# CH585M-R1.net
KiCad netlist of a schematic drawn in Altium Designer
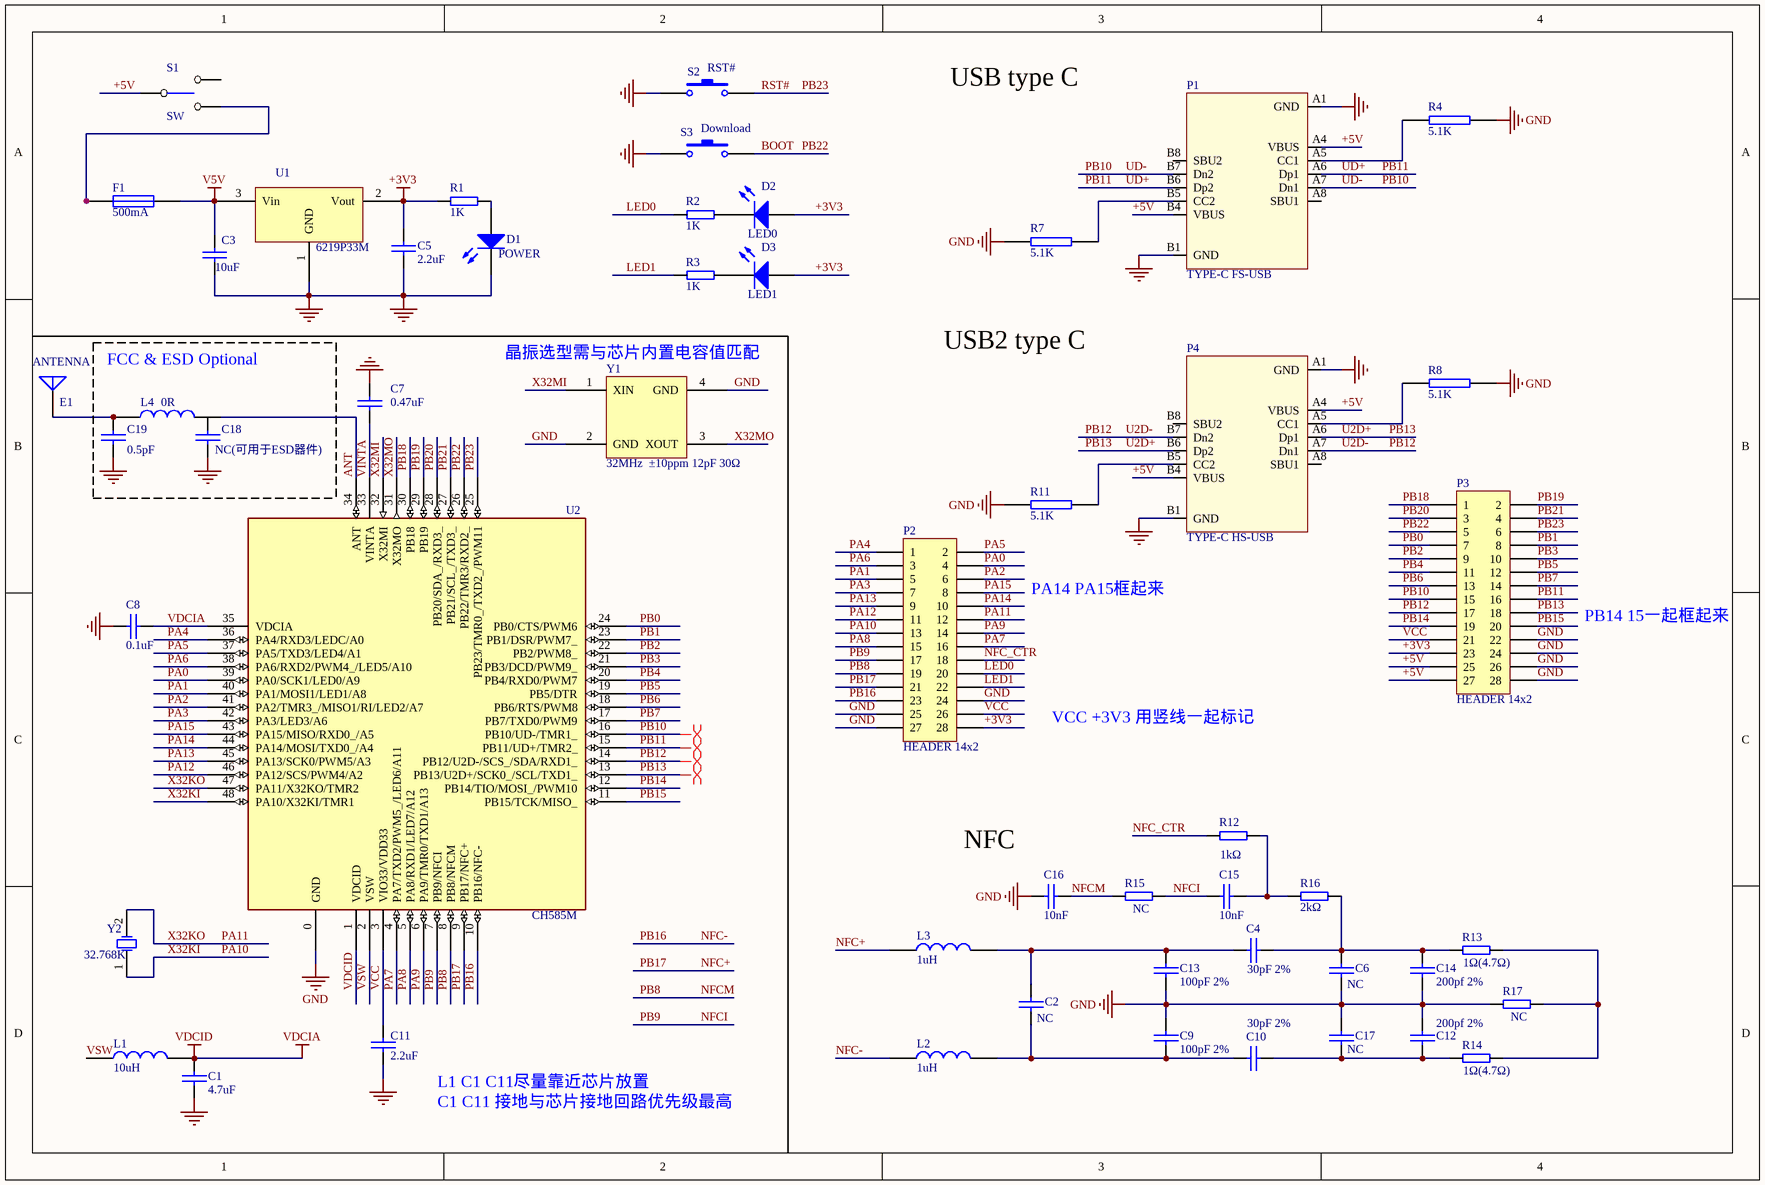
[diagram p0: CH585M-R1.SchDoc]

(export (version "E")
  (design (tool "Eeschema 10.0.6"))
  (components
    (comp (ref "C1")
      (value "4.7uF")
      (footprint "0402_C")
      (description "Capacitor")
      (libsource (lib "") (part "CAP_1"))
    )
    (comp (ref "C2")
      (value "NC")
      (footprint "0402_C")
      (description "Capacitor")
      (libsource (lib "wch_sch_others") (part "CAP"))
    )
    (comp (ref "C3")
      (value "10uF")
      (footprint "0603_C")
      (description "Capacitor")
      (libsource (lib "*") (part "CAP"))
    )
    (comp (ref "C4")
      (value "30pF 2%")
      (footprint "0402_C")
      (description "Capacitor")
      (libsource (lib "wch_sch_others") (part "CAP"))
    )
    (comp (ref "C5")
      (value "2.2uF")
      (footprint "0402_C")
      (description "Capacitor")
      (libsource (lib "*") (part "CAP"))
    )
    (comp (ref "C6")
      (value "NC")
      (footprint "0402_C")
      (description "Capacitor")
      (libsource (lib "wch_sch_others") (part "CAP"))
    )
    (comp (ref "C7")
      (value "0.47uF")
      (footprint "0402_C")
      (description "Capacitor")
      (libsource (lib "*") (part "CAP"))
    )
    (comp (ref "C8")
      (value "0.1uF")
      (footprint "0402_C")
      (description "Capacitor")
      (libsource (lib "*") (part "CAP"))
    )
    (comp (ref "C9")
      (value "100pF 2%")
      (footprint "0402_C")
      (description "Capacitor")
      (libsource (lib "wch_sch_others") (part "CAP"))
    )
    (comp (ref "C10")
      (value "30pF 2%")
      (footprint "0402_C")
      (description "Capacitor")
      (libsource (lib "wch_sch_others") (part "CAP"))
    )
    (comp (ref "C11")
      (value "2.2uF")
      (footprint "0402_C")
      (description "Capacitor")
      (libsource (lib "*") (part "CAP"))
    )
    (comp (ref "C12")
      (value "200pf 2%")
      (footprint "0402_C")
      (description "Capacitor")
      (libsource (lib "wch_sch_others") (part "CAP"))
    )
    (comp (ref "C13")
      (value "100pF 2%")
      (footprint "0402_C")
      (description "Capacitor")
      (libsource (lib "wch_sch_others") (part "CAP"))
    )
    (comp (ref "C14")
      (value "200pf 2%")
      (footprint "0402_C")
      (description "Capacitor")
      (libsource (lib "wch_sch_others") (part "CAP"))
    )
    (comp (ref "C15")
      (value "10nF")
      (footprint "0402_C")
      (description "Capacitor")
      (libsource (lib "wch_sch_others") (part "CAP"))
    )
    (comp (ref "C16")
      (value "10nF")
      (footprint "0402_C")
      (description "Capacitor")
      (libsource (lib "wch_sch_others") (part "CAP"))
    )
    (comp (ref "C17")
      (value "NC")
      (footprint "0402_C")
      (description "Capacitor")
      (libsource (lib "wch_sch_others") (part "CAP"))
    )
    (comp (ref "C18")
      (value "NC(可用于ESD器件)")
      (footprint "0402_C")
      (description "Capacitor")
      (libsource (lib "*") (part "CAP"))
    )
    (comp (ref "C19")
      (value "0.5pF")
      (footprint "0402_C")
      (description "Capacitor")
      (libsource (lib "") (part "CAP_1"))
    )
    (comp (ref "D1")
      (value "POWER")
      (footprint "0603+")
      (description "Typical INFRARED GaAs LED")
      (fields (field (name "PUBLISHER") "Altium Limited"))
      (libsource (lib "") (part "LED0_1"))
    )
    (comp (ref "D2")
      (value "LED0")
      (footprint "0603+")
      (description "Typical INFRARED GaAs LED")
      (fields (field (name "PUBLISHER") "Altium Limited"))
      (libsource (lib "Miscellaneous Devices") (part "LED0"))
    )
    (comp (ref "D3")
      (value "LED1")
      (footprint "0603+")
      (description "Typical INFRARED GaAs LED")
      (fields (field (name "PUBLISHER") "Altium Limited"))
      (libsource (lib "Miscellaneous Devices") (part "LED0"))
    )
    (comp (ref "E1")
      (value "ANTENNA")
      (footprint "ANT-F-1-2.4G-1.6mmFR4")
      (description "Generic Antenna")
      (libsource (lib "*") (part "ANTENNA"))
    )
    (comp (ref "F1")
      (value "500mA")
      (footprint "0603")
      (description "Fuse")
      (libsource (lib "*") (part "FUSE1"))
    )
    (comp (ref "L1") (value "10uH") (footprint "SMD_2x2mm") (libsource (lib "*") (part "INDUCTOR")))
    (comp (ref "L2") (value "1uH") (footprint "0603") (libsource (lib "*") (part "INDUCTOR")))
    (comp (ref "L3") (value "1uH") (footprint "0603") (libsource (lib "*") (part "INDUCTOR")))
    (comp (ref "L4") (value "0R") (footprint "SMD_2x2mm") (libsource (lib "*") (part "INDUCTOR")))
    (comp (ref "P1")
      (value "TYPE-C FS-USB")
      (footprint "TYPE-C-Receptacle-2.0")
      (description "Type-C USB2.0 母座")
      (libsource (lib "Miscellaneous SCH Lib") (part "TYPE-C-Receptacle-2.0"))
    )
    (comp (ref "P2")
      (value "HEADER 14x2")
      (footprint "MYPCB:IDC28-2.54MM")
      (description "Header, 14-Pin, Dual row")
      (libsource (lib "wch_sch_others") (part "HEADER 14x2"))
    )
    (comp (ref "P3")
      (value "HEADER 14x2")
      (footprint "MYPCB:IDC28-2.54MM")
      (description "Header, 14-Pin, Dual row")
      (libsource (lib "wch_sch_others") (part "HEADER 14x2"))
    )
    (comp (ref "P4")
      (value "TYPE-C HS-USB")
      (footprint "TYPE-C-Receptacle-2.0")
      (description "Type-C USB2.0 母座")
      (libsource (lib "Miscellaneous SCH Lib") (part "TYPE-C-Receptacle-2.0"))
    )
    (comp (ref "R1") (value "1K") (footprint "0402") (libsource (lib "wch_sch_others") (part "RES")))
    (comp (ref "R2") (value "1K") (footprint "0402") (libsource (lib "wch_sch_others") (part "RES")))
    (comp (ref "R3") (value "1K") (footprint "0402") (libsource (lib "wch_sch_others") (part "RES")))
    (comp (ref "R4") (value "5.1K") (footprint "0402") (libsource (lib "*") (part "RES2")))
    (comp (ref "R7") (value "5.1K") (footprint "0402") (libsource (lib "*") (part "RES2")))
    (comp (ref "R8") (value "5.1K") (footprint "0402") (libsource (lib "*") (part "RES2")))
    (comp (ref "R11") (value "5.1K") (footprint "0402") (libsource (lib "*") (part "RES2")))
    (comp (ref "R12") (value "1kΩ") (footprint "0402") (libsource (lib "") (part "RES_1")))
    (comp (ref "R13") (value "1Ω(4.7Ω)") (footprint "0402") (libsource (lib "") (part "RES_1")))
    (comp (ref "R14") (value "1Ω(4.7Ω)") (footprint "0402") (libsource (lib "") (part "RES_1")))
    (comp (ref "R15") (value "NC") (footprint "0402") (libsource (lib "") (part "RES_1")))
    (comp (ref "R16") (value "2kΩ") (footprint "0402") (libsource (lib "") (part "RES_1")))
    (comp (ref "R17") (value "NC") (footprint "0402") (libsource (lib "") (part "RES_1")))
    (comp (ref "S1") (value "SW") (footprint "SW1") (libsource (lib "MYSCH") (part "SW")))
    (comp (ref "S2")
      (value "RST#")
      (footprint "SMD_6.1x3.65x2.5mm-KEY")
      (description "Switch")
      (fields (field (name "PUBLISHER") "Altium Limited"))
      (libsource (lib "*") (part "SW-PB"))
    )
    (comp (ref "S3")
      (value "Download")
      (footprint "SMD_6.1x3.65x2.5mm-KEY")
      (description "Switch")
      (fields (field (name "PUBLISHER") "Altium Limited"))
      (libsource (lib "*") (part "SW-PB"))
    )
    (comp (ref "U1")
      (value "6219P33M")
      (footprint "SOT-23")
      (libsource (lib "wch_sch_others") (part "6219P33M"))
    )
    (comp (ref "U2")
      (value "CH585M")
      (footprint "QFN48_5X5")
      (description "RISC-V MCU with BLE/HSUSB/USB/NFC/ADC/PWM/2*SPI/I2C/4*UART/LCD")
      (libsource (lib "CHXXX") (part "CH585M"))
    )
    (comp (ref "Y1")
      (value "32MHz  ±10ppm 12pF 30Ω")
      (footprint "XT3225")
      (libsource (lib "wch_sch_others") (part "晶体"))
    )
    (comp (ref "Y2")
      (value "32.768K")
      (footprint "fc-135")
      (description "Crystal Oscillator")
      (fields (field (name "PUBLISHER") "Altium Limited"))
      (libsource (lib "*") (part "XTAL"))
    )
  )
  (nets
    (net (code "1") (name "+3V3") (class "Default")
      (node (ref "C5") (pin "1") (pinfunction "1_1") (pintype "passive"))
      (node (ref "D2") (pin "1") (pinfunction "A_1") (pintype "passive"))
      (node (ref "D3") (pin "1") (pinfunction "A_1") (pintype "passive"))
      (node (ref "P2") (pin "28") (pinfunction "28_28") (pintype "passive"))
      (node (ref "P3") (pin "23") (pinfunction "23_23") (pintype "passive"))
      (node (ref "R1") (pin "2") (pintype "passive"))
      (node (ref "U1") (pin "2") (pinfunction "Vout_2") (pintype "passive"))
    )
    (net (code "2") (name "/+5V") (class "Default")
      (node (ref "P1") (pin "A4") (pinfunction "VBUS_A4") (pintype "passive"))
      (node (ref "P1") (pin "B4") (pinfunction "VBUS_B4") (pintype "passive"))
      (node (ref "P3") (pin "25") (pinfunction "25_25") (pintype "passive"))
      (node (ref "P3") (pin "27") (pinfunction "27_27") (pintype "passive"))
      (node (ref "P4") (pin "A4") (pinfunction "VBUS_A4") (pintype "passive"))
      (node (ref "P4") (pin "B4") (pinfunction "VBUS_B4") (pintype "passive"))
      (node (ref "S1") (pin "1") (pinfunction "1_1") (pintype "passive"))
    )
    (net (code "3") (name "/ANT") (class "Default")
      (node (ref "L4") (pin "2") (pinfunction "2_2") (pintype "passive"))
      (node (ref "U2") (pin "34") (pinfunction "ANT_34") (pintype "bidirectional"))
    )
    (net (code "4") (name "/BOOT") (class "Default")
      (node (ref "P3") (pin "5") (pinfunction "5_5") (pintype "passive"))
      (node (ref "S3") (pin "2") (pinfunction "2_2") (pintype "passive"))
      (node (ref "U2") (pin "26") (pinfunction "PB22/TMR3/RXD2__26") (pintype "bidirectional"))
    )
    (net (code "5") (name "/LED0") (class "Default")
      (node (ref "P2") (pin "20") (pinfunction "20_20") (pintype "passive"))
      (node (ref "R2") (pin "1") (pintype "passive"))
    )
    (net (code "6") (name "/LED1") (class "Default")
      (node (ref "P2") (pin "22") (pinfunction "22_22") (pintype "passive"))
      (node (ref "R3") (pin "1") (pintype "passive"))
    )
    (net (code "7") (name "/NFC+") (class "Default")
      (node (ref "L3") (pin "1") (pinfunction "1_1") (pintype "passive"))
      (node (ref "P2") (pin "21") (pinfunction "21_21") (pintype "passive"))
      (node (ref "U2") (pin "9") (pinfunction "PB17/NFC+_9") (pintype "bidirectional"))
    )
    (net (code "8") (name "/NFC-") (class "Default")
      (node (ref "L2") (pin "1") (pinfunction "1_1") (pintype "passive"))
      (node (ref "P2") (pin "23") (pinfunction "23_23") (pintype "passive"))
      (node (ref "U2") (pin "10") (pinfunction "PB16/NFC-_10") (pintype "bidirectional"))
    )
    (net (code "9") (name "/NFCI") (class "Default")
      (node (ref "C15") (pin "1") (pinfunction "1_1") (pintype "passive"))
      (node (ref "P2") (pin "17") (pinfunction "17_17") (pintype "passive"))
      (node (ref "R15") (pin "1") (pintype "passive"))
      (node (ref "U2") (pin "7") (pinfunction "PB9/NFCI_7") (pintype "bidirectional"))
    )
    (net (code "10") (name "/NFCM") (class "Default")
      (node (ref "C16") (pin "1") (pinfunction "1_1") (pintype "passive"))
      (node (ref "P2") (pin "19") (pinfunction "19_19") (pintype "passive"))
      (node (ref "R15") (pin "2") (pintype "passive"))
      (node (ref "U2") (pin "8") (pinfunction "PB8/NFCM_8") (pintype "bidirectional"))
    )
    (net (code "11") (name "/NFC_CTR") (class "Default")
      (node (ref "P2") (pin "18") (pinfunction "18_18") (pintype "passive"))
      (node (ref "R12") (pin "2") (pintype "passive"))
    )
    (net (code "12") (name "/PA0") (class "Default")
      (node (ref "P2") (pin "4") (pinfunction "4_4") (pintype "passive"))
      (node (ref "U2") (pin "39") (pinfunction "PA0/SCK1/LED0/A9_39") (pintype "bidirectional"))
    )
    (net (code "13") (name "/PA1") (class "Default")
      (node (ref "P2") (pin "5") (pinfunction "5_5") (pintype "passive"))
      (node (ref "U2") (pin "40") (pinfunction "PA1/MOSI1/LED1/A8_40") (pintype "bidirectional"))
    )
    (net (code "14") (name "/PA2") (class "Default")
      (node (ref "P2") (pin "6") (pinfunction "6_6") (pintype "passive"))
      (node (ref "U2") (pin "41") (pinfunction "PA2/TMR3_/MISO1/RI/LED2/A7_41") (pintype "bidirectional"))
    )
    (net (code "15") (name "/PA3") (class "Default")
      (node (ref "P2") (pin "7") (pinfunction "7_7") (pintype "passive"))
      (node (ref "U2") (pin "42") (pinfunction "PA3/LED3/A6_42") (pintype "bidirectional"))
    )
    (net (code "16") (name "/PA4") (class "Default")
      (node (ref "P2") (pin "1") (pinfunction "1_1") (pintype "passive"))
      (node (ref "U2") (pin "36") (pinfunction "PA4/RXD3/LEDC/A0_36") (pintype "bidirectional"))
    )
    (net (code "17") (name "/PA5") (class "Default")
      (node (ref "P2") (pin "2") (pinfunction "2_2") (pintype "passive"))
      (node (ref "U2") (pin "37") (pinfunction "PA5/TXD3/LED4/A1_37") (pintype "bidirectional"))
    )
    (net (code "18") (name "/PA6") (class "Default")
      (node (ref "P2") (pin "3") (pinfunction "3_3") (pintype "passive"))
      (node (ref "U2") (pin "38") (pinfunction "PA6/RXD2/PWM4_/LED5/A10_38") (pintype "bidirectional"))
    )
    (net (code "19") (name "/PA7") (class "Default")
      (node (ref "P2") (pin "16") (pinfunction "16_16") (pintype "passive"))
      (node (ref "U2") (pin "4") (pinfunction "PA7/TXD2/PWM5_/LED6/A11_4") (pintype "bidirectional"))
    )
    (net (code "20") (name "/PA8") (class "Default")
      (node (ref "P2") (pin "15") (pinfunction "15_15") (pintype "passive"))
      (node (ref "U2") (pin "5") (pinfunction "PA8/RXD1/LED7/A12_5") (pintype "bidirectional"))
    )
    (net (code "21") (name "/PA9") (class "Default")
      (node (ref "P2") (pin "14") (pinfunction "14_14") (pintype "passive"))
      (node (ref "U2") (pin "6") (pinfunction "PA9/TMR0/TXD1/A13_6") (pintype "bidirectional"))
    )
    (net (code "22") (name "/PA10") (class "Default")
      (node (ref "P2") (pin "13") (pinfunction "13_13") (pintype "passive"))
      (node (ref "U2") (pin "48") (pinfunction "PA10/X32KI/TMR1_48") (pintype "bidirectional"))
      (node (ref "Y2") (pin "1") (pinfunction "OSC1_1") (pintype "passive"))
    )
    (net (code "23") (name "/PA11") (class "Default")
      (node (ref "P2") (pin "12") (pinfunction "12_12") (pintype "passive"))
      (node (ref "U2") (pin "47") (pinfunction "PA11/X32KO/TMR2_47") (pintype "bidirectional"))
      (node (ref "Y2") (pin "2") (pinfunction "OSC2_2") (pintype "passive"))
    )
    (net (code "24") (name "/PA12") (class "Default")
      (node (ref "P2") (pin "11") (pinfunction "11_11") (pintype "passive"))
      (node (ref "U2") (pin "46") (pinfunction "PA12/SCS/PWM4/A2_46") (pintype "bidirectional"))
    )
    (net (code "25") (name "/PA13") (class "Default")
      (node (ref "P2") (pin "9") (pinfunction "9_9") (pintype "passive"))
      (node (ref "U2") (pin "45") (pinfunction "PA13/SCK0/PWM5/A3_45") (pintype "bidirectional"))
    )
    (net (code "26") (name "/PA14") (class "Default")
      (node (ref "P2") (pin "10") (pinfunction "10_10") (pintype "passive"))
      (node (ref "U2") (pin "44") (pinfunction "PA14/MOSI/TXD0_/A4_44") (pintype "bidirectional"))
    )
    (net (code "27") (name "/PA15") (class "Default")
      (node (ref "P2") (pin "8") (pinfunction "8_8") (pintype "passive"))
      (node (ref "U2") (pin "43") (pinfunction "PA15/MISO/RXD0_/A5_43") (pintype "bidirectional"))
    )
    (net (code "28") (name "/PB0") (class "Default")
      (node (ref "P3") (pin "7") (pinfunction "7_7") (pintype "passive"))
      (node (ref "U2") (pin "24") (pinfunction "PB0/CTS/PWM6_24") (pintype "bidirectional"))
    )
    (net (code "29") (name "/PB1") (class "Default")
      (node (ref "P3") (pin "8") (pinfunction "8_8") (pintype "passive"))
      (node (ref "U2") (pin "23") (pinfunction "PB1/DSR/PWM7__23") (pintype "bidirectional"))
    )
    (net (code "30") (name "/PB2") (class "Default")
      (node (ref "P3") (pin "9") (pinfunction "9_9") (pintype "passive"))
      (node (ref "U2") (pin "22") (pinfunction "PB2/PWM8__22") (pintype "bidirectional"))
    )
    (net (code "31") (name "/PB3") (class "Default")
      (node (ref "P3") (pin "10") (pinfunction "10_10") (pintype "passive"))
      (node (ref "U2") (pin "21") (pinfunction "PB3/DCD/PWM9__21") (pintype "bidirectional"))
    )
    (net (code "32") (name "/PB4") (class "Default")
      (node (ref "P3") (pin "11") (pinfunction "11_11") (pintype "passive"))
      (node (ref "U2") (pin "20") (pinfunction "PB4/RXD0/PWM7_20") (pintype "bidirectional"))
    )
    (net (code "33") (name "/PB5") (class "Default")
      (node (ref "P3") (pin "12") (pinfunction "12_12") (pintype "passive"))
      (node (ref "U2") (pin "19") (pinfunction "PB5/DTR_19") (pintype "bidirectional"))
    )
    (net (code "34") (name "/PB6") (class "Default")
      (node (ref "P3") (pin "13") (pinfunction "13_13") (pintype "passive"))
      (node (ref "U2") (pin "18") (pinfunction "PB6/RTS/PWM8_18") (pintype "bidirectional"))
    )
    (net (code "35") (name "/PB7") (class "Default")
      (node (ref "P3") (pin "14") (pinfunction "14_14") (pintype "passive"))
      (node (ref "U2") (pin "17") (pinfunction "PB7/TXD0/PWM9_17") (pintype "bidirectional"))
    )
    (net (code "36") (name "/PB10") (class "Default")
      (node (ref "P1") (pin "A7") (pinfunction "Dn1_A7") (pintype "passive"))
      (node (ref "P1") (pin "B7") (pinfunction "Dn2_B7") (pintype "passive"))
      (node (ref "P3") (pin "15") (pinfunction "15_15") (pintype "passive"))
      (node (ref "U2") (pin "16") (pinfunction "PB10/UD-/TMR1__16") (pintype "bidirectional"))
    )
    (net (code "37") (name "/PB11") (class "Default")
      (node (ref "P1") (pin "A6") (pinfunction "Dp1_A6") (pintype "passive"))
      (node (ref "P1") (pin "B6") (pinfunction "Dp2_B6") (pintype "passive"))
      (node (ref "P3") (pin "16") (pinfunction "16_16") (pintype "passive"))
      (node (ref "U2") (pin "15") (pinfunction "PB11/UD+/TMR2__15") (pintype "bidirectional"))
    )
    (net (code "38") (name "/PB12") (class "Default")
      (node (ref "P3") (pin "17") (pinfunction "17_17") (pintype "passive"))
      (node (ref "P4") (pin "A7") (pinfunction "Dn1_A7") (pintype "passive"))
      (node (ref "P4") (pin "B7") (pinfunction "Dn2_B7") (pintype "passive"))
      (node (ref "U2") (pin "14") (pinfunction "PB12/U2D-/SCS_/SDA/RXD1__14") (pintype "bidirectional"))
    )
    (net (code "39") (name "/PB13") (class "Default")
      (node (ref "P3") (pin "18") (pinfunction "18_18") (pintype "passive"))
      (node (ref "P4") (pin "A6") (pinfunction "Dp1_A6") (pintype "passive"))
      (node (ref "P4") (pin "B6") (pinfunction "Dp2_B6") (pintype "passive"))
      (node (ref "U2") (pin "13") (pinfunction "PB13/U2D+/SCK0_/SCL/TXD1__13") (pintype "bidirectional"))
    )
    (net (code "40") (name "/PB14") (class "Default")
      (node (ref "P3") (pin "19") (pinfunction "19_19") (pintype "passive"))
      (node (ref "U2") (pin "12") (pinfunction "PB14/TIO/MOSI_/PWM10_12") (pintype "bidirectional"))
    )
    (net (code "41") (name "/PB15") (class "Default")
      (node (ref "P3") (pin "20") (pinfunction "20_20") (pintype "passive"))
      (node (ref "U2") (pin "11") (pinfunction "PB15/TCK/MISO__11") (pintype "bidirectional"))
    )
    (net (code "42") (name "/PB18") (class "Default")
      (node (ref "P3") (pin "1") (pinfunction "1_1") (pintype "passive"))
      (node (ref "U2") (pin "30") (pinfunction "PB18_30") (pintype "bidirectional"))
    )
    (net (code "43") (name "/PB19") (class "Default")
      (node (ref "P3") (pin "2") (pinfunction "2_2") (pintype "passive"))
      (node (ref "U2") (pin "29") (pinfunction "PB19_29") (pintype "bidirectional"))
    )
    (net (code "44") (name "/PB20") (class "Default")
      (node (ref "P3") (pin "3") (pinfunction "3_3") (pintype "passive"))
      (node (ref "U2") (pin "28") (pinfunction "PB20/SDA_/RXD3__28") (pintype "bidirectional"))
    )
    (net (code "45") (name "/PB21") (class "Default")
      (node (ref "P3") (pin "4") (pinfunction "4_4") (pintype "passive"))
      (node (ref "U2") (pin "27") (pinfunction "PB21/SCL_/TXD3__27") (pintype "bidirectional"))
    )
    (net (code "46") (name "/PB23") (class "Default")
      (node (ref "P3") (pin "6") (pinfunction "6_6") (pintype "passive"))
      (node (ref "S2") (pin "2") (pinfunction "2_2") (pintype "passive"))
      (node (ref "U2") (pin "25") (pinfunction "PB23/TMR0_/TXD2_/PWM11_25") (pintype "bidirectional"))
    )
    (net (code "47") (name "/VCC") (class "Default")
      (node (ref "C11") (pin "2") (pinfunction "2_2") (pintype "passive"))
      (node (ref "P2") (pin "26") (pinfunction "26_26") (pintype "passive"))
      (node (ref "P3") (pin "21") (pinfunction "21_21") (pintype "passive"))
      (node (ref "U2") (pin "3") (pinfunction "VIO33/VDD33_3") (pintype "power_in"))
    )
    (net (code "48") (name "/VINTA") (class "Default")
      (node (ref "C7") (pin "1") (pinfunction "1_1") (pintype "passive"))
      (node (ref "U2") (pin "33") (pinfunction "VINTA_33") (pintype "power_in"))
    )
    (net (code "49") (name "/VSW") (class "Default")
      (node (ref "L1") (pin "1") (pinfunction "1_1") (pintype "passive"))
      (node (ref "U2") (pin "2") (pinfunction "VSW_2") (pintype "power_in"))
    )
    (net (code "50") (name "/X32MI") (class "Default")
      (node (ref "U2") (pin "32") (pinfunction "X32MI_32") (pintype "input"))
      (node (ref "Y1") (pin "1") (pinfunction "XIN_1") (pintype "passive"))
    )
    (net (code "51") (name "/X32MO") (class "Default")
      (node (ref "U2") (pin "31") (pinfunction "X32MO_31") (pintype "output"))
      (node (ref "Y1") (pin "3") (pinfunction "XOUT_3") (pintype "passive"))
    )
    (net (code "52") (name "GND") (class "Default")
      (node (ref "C1") (pin "1") (pinfunction "1_1") (pintype "passive"))
      (node (ref "C11") (pin "1") (pinfunction "1_1") (pintype "passive"))
      (node (ref "C12") (pin "2") (pinfunction "2_2") (pintype "passive"))
      (node (ref "C13") (pin "1") (pinfunction "1_1") (pintype "passive"))
      (node (ref "C14") (pin "1") (pinfunction "1_1") (pintype "passive"))
      (node (ref "C16") (pin "2") (pinfunction "2_2") (pintype "passive"))
      (node (ref "C17") (pin "2") (pinfunction "2_2") (pintype "passive"))
      (node (ref "C18") (pin "1") (pinfunction "1_1") (pintype "passive"))
      (node (ref "C19") (pin "1") (pinfunction "1_1") (pintype "passive"))
      (node (ref "C3") (pin "2") (pinfunction "2_2") (pintype "passive"))
      (node (ref "C5") (pin "2") (pinfunction "2_2") (pintype "passive"))
      (node (ref "C6") (pin "1") (pinfunction "1_1") (pintype "passive"))
      (node (ref "C7") (pin "2") (pinfunction "2_2") (pintype "passive"))
      (node (ref "C8") (pin "2") (pinfunction "2_2") (pintype "passive"))
      (node (ref "C9") (pin "2") (pinfunction "2_2") (pintype "passive"))
      (node (ref "D1") (pin "2") (pinfunction "K_2") (pintype "passive"))
      (node (ref "P1") (pin "A1") (pinfunction "GND_A1") (pintype "passive"))
      (node (ref "P1") (pin "B1") (pinfunction "GND_B1") (pintype "passive"))
      (node (ref "P2") (pin "24") (pinfunction "24_24") (pintype "passive"))
      (node (ref "P2") (pin "25") (pinfunction "25_25") (pintype "passive"))
      (node (ref "P2") (pin "27") (pinfunction "27_27") (pintype "passive"))
      (node (ref "P3") (pin "22") (pinfunction "22_22") (pintype "passive"))
      (node (ref "P3") (pin "24") (pinfunction "24_24") (pintype "passive"))
      (node (ref "P3") (pin "26") (pinfunction "26_26") (pintype "passive"))
      (node (ref "P3") (pin "28") (pinfunction "28_28") (pintype "passive"))
      (node (ref "P4") (pin "A1") (pinfunction "GND_A1") (pintype "passive"))
      (node (ref "P4") (pin "B1") (pinfunction "GND_B1") (pintype "passive"))
      (node (ref "R11") (pin "2") (pinfunction "2_2") (pintype "passive"))
      (node (ref "R17") (pin "2") (pintype "passive"))
      (node (ref "R4") (pin "1") (pinfunction "1_1") (pintype "passive"))
      (node (ref "R7") (pin "2") (pinfunction "2_2") (pintype "passive"))
      (node (ref "R8") (pin "1") (pinfunction "1_1") (pintype "passive"))
      (node (ref "S2") (pin "1") (pinfunction "1_1") (pintype "passive"))
      (node (ref "S3") (pin "1") (pinfunction "1_1") (pintype "passive"))
      (node (ref "U1") (pin "1") (pinfunction "GND_1") (pintype "passive"))
      (node (ref "U2") (pin "0") (pinfunction "GND_0") (pintype "power_in"))
      (node (ref "Y1") (pin "2") (pinfunction "GND_2") (pintype "passive"))
      (node (ref "Y1") (pin "4") (pinfunction "GND_4") (pintype "passive"))
    )
    (net (code "53") (name "Net-(C10-Pad1)") (class "Default")
      (node (ref "C10") (pin "1") (pinfunction "1_1") (pintype "passive"))
      (node (ref "C2") (pin "1") (pinfunction "1_1") (pintype "passive"))
      (node (ref "C9") (pin "1") (pinfunction "1_1") (pintype "passive"))
      (node (ref "L2") (pin "2") (pinfunction "2_2") (pintype "passive"))
    )
    (net (code "54") (name "Net-(C10-Pad2)") (class "Default")
      (node (ref "C10") (pin "2") (pinfunction "2_2") (pintype "passive"))
      (node (ref "C12") (pin "1") (pinfunction "1_1") (pintype "passive"))
      (node (ref "C17") (pin "1") (pinfunction "1_1") (pintype "passive"))
      (node (ref "R14") (pin "1") (pintype "passive"))
    )
    (net (code "55") (name "Net-(C13-Pad2)") (class "Default")
      (node (ref "C13") (pin "2") (pinfunction "2_2") (pintype "passive"))
      (node (ref "C2") (pin "2") (pinfunction "2_2") (pintype "passive"))
      (node (ref "C4") (pin "1") (pinfunction "1_1") (pintype "passive"))
      (node (ref "L3") (pin "2") (pinfunction "2_2") (pintype "passive"))
    )
    (net (code "56") (name "Net-(C14-Pad2)") (class "Default")
      (node (ref "C14") (pin "2") (pinfunction "2_2") (pintype "passive"))
      (node (ref "C4") (pin "2") (pinfunction "2_2") (pintype "passive"))
      (node (ref "C6") (pin "2") (pinfunction "2_2") (pintype "passive"))
      (node (ref "R13") (pin "1") (pintype "passive"))
      (node (ref "R16") (pin "1") (pintype "passive"))
    )
    (net (code "57") (name "Net-(C15-Pad2)") (class "Default")
      (node (ref "C15") (pin "2") (pinfunction "2_2") (pintype "passive"))
      (node (ref "R12") (pin "1") (pintype "passive"))
      (node (ref "R16") (pin "2") (pintype "passive"))
    )
    (net (code "58") (name "Net-(D1-A)") (class "Default")
      (node (ref "D1") (pin "1") (pinfunction "A_1") (pintype "passive"))
      (node (ref "R1") (pin "1") (pintype "passive"))
    )
    (net (code "59") (name "Net-(D2-K)") (class "Default")
      (node (ref "D2") (pin "2") (pinfunction "K_2") (pintype "passive"))
      (node (ref "R2") (pin "2") (pintype "passive"))
    )
    (net (code "60") (name "Net-(D3-K)") (class "Default")
      (node (ref "D3") (pin "2") (pinfunction "K_2") (pintype "passive"))
      (node (ref "R3") (pin "2") (pintype "passive"))
    )
    (net (code "61") (name "Net-(E1-A)") (class "Default")
      (node (ref "C19") (pin "2") (pinfunction "2_2") (pintype "passive"))
      (node (ref "E1") (pin "1") (pinfunction "A_1") (pintype "passive"))
      (node (ref "L4") (pin "1") (pinfunction "1_1") (pintype "passive"))
    )
    (net (code "62") (name "Net-(F1-Pad1)") (class "Default")
      (node (ref "F1") (pin "1") (pinfunction "1_1") (pintype "passive"))
      (node (ref "S1") (pin "2") (pinfunction "2_2") (pintype "passive"))
    )
    (net (code "63") (name "Net-(P1-CC1)") (class "Default")
      (node (ref "P1") (pin "A5") (pinfunction "CC1_A5") (pintype "passive"))
      (node (ref "R4") (pin "2") (pinfunction "2_2") (pintype "passive"))
    )
    (net (code "64") (name "Net-(P1-CC2)") (class "Default")
      (node (ref "P1") (pin "B5") (pinfunction "CC2_B5") (pintype "passive"))
      (node (ref "R7") (pin "1") (pinfunction "1_1") (pintype "passive"))
    )
    (net (code "65") (name "Net-(P4-CC1)") (class "Default")
      (node (ref "P4") (pin "A5") (pinfunction "CC1_A5") (pintype "passive"))
      (node (ref "R8") (pin "2") (pinfunction "2_2") (pintype "passive"))
    )
    (net (code "66") (name "Net-(P4-CC2)") (class "Default")
      (node (ref "P4") (pin "B5") (pinfunction "CC2_B5") (pintype "passive"))
      (node (ref "R11") (pin "1") (pinfunction "1_1") (pintype "passive"))
    )
    (net (code "67") (name "Net-(R13-Pad2)") (class "Default")
      (node (ref "R13") (pin "2") (pintype "passive"))
      (node (ref "R14") (pin "2") (pintype "passive"))
      (node (ref "R17") (pin "1") (pintype "passive"))
    )
    (net (code "68") (name "V5V") (class "Default")
      (node (ref "C3") (pin "1") (pinfunction "1_1") (pintype "passive"))
      (node (ref "F1") (pin "2") (pinfunction "2_2") (pintype "passive"))
      (node (ref "U1") (pin "3") (pinfunction "Vin_3") (pintype "passive"))
    )
    (net (code "69") (name "VDCIA") (class "Default")
      (node (ref "C1") (pin "2") (pinfunction "2_2") (pintype "passive"))
      (node (ref "C8") (pin "1") (pinfunction "1_1") (pintype "passive"))
      (node (ref "L1") (pin "2") (pinfunction "2_2") (pintype "passive"))
      (node (ref "U2") (pin "1") (pinfunction "VDCID_1") (pintype "power_in"))
      (node (ref "U2") (pin "35") (pinfunction "VDCIA_35") (pintype "power_in"))
    )
    (net (code "70") (name "unconnected-(C18-Pad2)") (class "Default")
      (node (ref "C18") (pin "2") (pinfunction "2_2") (pintype "passive"))
    )
    (net (code "71") (name "unconnected-(P1-SBU1-PadA8)") (class "Default")
      (node (ref "P1") (pin "A8") (pinfunction "SBU1_A8") (pintype "passive"))
    )
    (net (code "72") (name "unconnected-(P1-SBU2-PadB8)") (class "Default")
      (node (ref "P1") (pin "B8") (pinfunction "SBU2_B8") (pintype "passive"))
    )
    (net (code "73") (name "unconnected-(P4-SBU1-PadA8)") (class "Default")
      (node (ref "P4") (pin "A8") (pinfunction "SBU1_A8") (pintype "passive"))
    )
    (net (code "74") (name "unconnected-(P4-SBU2-PadB8)") (class "Default")
      (node (ref "P4") (pin "B8") (pinfunction "SBU2_B8") (pintype "passive"))
    )
    (net (code "75") (name "unconnected-(S1-Pad3)") (class "Default")
      (node (ref "S1") (pin "3") (pinfunction "3_3") (pintype "passive"))
    )
  )
)
